# 102709.net
KiCad netlist of a schematic drawn in Altium Designer
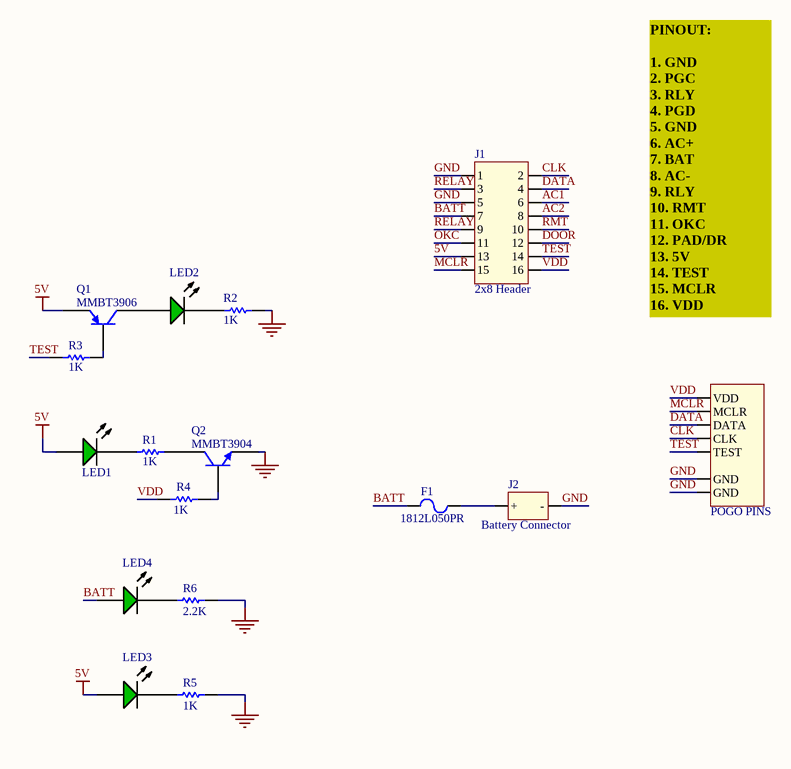
[diagram p0: 102709.SchDoc]

(export (version "E")
  (design (tool "Eeschema 10.0.6"))
  (components
    (comp (ref "F1")
      (value "1812L050PR")
      (footprint "LFUS-1812L050_V")
      (fields (field (name "TOLERANCE") "1%"))
      (libsource (lib "Altium Content Vault") (part "CMP-1700-00002-1"))
    )
    (comp (ref "J1")
      (value "2x8 Header")
      (footprint "2x9_header")
      (libsource (lib "102709") (part "2x9 Header"))
    )
    (comp (ref "J2")
      (value "Battery Connector")
      (footprint "Battery Connector")
      (libsource (lib "102709") (part "Battery Connector"))
    )
    (comp (ref "LED1")
      (value "HSMG-C150")
      (footprint "AVAG-HSMX-C150_V")
      (description "Chip LED, Green, 65 mW, 25 mA, -40 to 85 degC, 2-Pin SMD, RoHS, Tape and Reel")
      (fields (field (name "MANUFACTURER") "Avago"))
      (libsource (lib "altium-import") (part "root_0__Altium Content Vault"))
    )
    (comp (ref "LED2")
      (value "HSMG-C150")
      (footprint "AVAG-HSMX-C150_V")
      (description "Chip LED, Green, 65 mW, 25 mA, -40 to 85 degC, 2-Pin SMD, RoHS, Tape and Reel")
      (fields (field (name "MANUFACTURER") "Avago"))
      (libsource (lib "altium-import") (part "root_0__Altium Content Vault"))
    )
    (comp (ref "LED3")
      (value "HSMG-C150")
      (footprint "AVAG-HSMX-C150_V")
      (description "Chip LED, Green, 65 mW, 25 mA, -40 to 85 degC, 2-Pin SMD, RoHS, Tape and Reel")
      (fields (field (name "MANUFACTURER") "Avago"))
      (libsource (lib "altium-import") (part "root_0__Altium Content Vault"))
    )
    (comp (ref "LED4")
      (value "HSMG-C150")
      (footprint "AVAG-HSMX-C150_V")
      (description "Chip LED, Green, 65 mW, 25 mA, -40 to 85 degC, 2-Pin SMD, RoHS, Tape and Reel")
      (fields (field (name "MANUFACTURER") "Avago"))
      (libsource (lib "altium-import") (part "root_0__Altium Content Vault"))
    )
    (comp (ref "P1")
      (value "POGO PINS")
      (footprint "EAX500 POGOS")
      (libsource (lib "102709") (part "EAX500 POGO"))
    )
    (comp (ref "Q1")
      (value "MMBT3906")
      (footprint "FAIR-SOT23-3_V")
      (description "PNP General-Purpose Amplifier, 40 V, 0.2 A, -55 to 150 degC, 3-Pin SOT23, RoHS, Tape and Reel")
      (fields (field (name "TOLERANCE") "20%"))
      (libsource (lib "Altium Content Vault") (part "CMP-1670-00011-1"))
    )
    (comp (ref "Q2")
      (value "MMBT3904")
      (footprint "FAIR-SOT23-3_V")
      (description "NPN General Purpose Amplifier, 40 V, 0.2 A, -55 to 150 degC, 3-Pin SOT23, RoHS, Tape and Reel")
      (fields (field (name "TOLERANCE") "30ppm"))
      (libsource (lib "Altium Content Vault") (part "CMP-1670-00008-1"))
    )
    (comp (ref "R1")
      (value "1K")
      (footprint "RESC0805(2012)_M")
      (description "Resistor")
      (fields (field (name "Comment") "Res1") (field (name "PUBLISHER") "Altium Limited"))
      (libsource (lib "Miscellaneous Devices") (part "Res1"))
    )
    (comp (ref "R2")
      (value "1K")
      (footprint "RESC0805(2012)_M")
      (description "Resistor")
      (fields (field (name "Comment") "Res1") (field (name "PUBLISHER") "Altium Limited"))
      (libsource (lib "Miscellaneous Devices") (part "Res1"))
    )
    (comp (ref "R3")
      (value "1K")
      (footprint "RESC0805(2012)_M")
      (description "Resistor")
      (fields (field (name "Comment") "Res1") (field (name "PUBLISHER") "Altium Limited"))
      (libsource (lib "Miscellaneous Devices") (part "Res1"))
    )
    (comp (ref "R4")
      (value "1K")
      (footprint "RESC0805(2012)_M")
      (description "Resistor")
      (fields (field (name "Comment") "Res1") (field (name "PUBLISHER") "Altium Limited"))
      (libsource (lib "Miscellaneous Devices") (part "Res1"))
    )
    (comp (ref "R5")
      (value "1K")
      (footprint "RESC0805(2012)_M")
      (description "Resistor")
      (fields (field (name "Comment") "Res1") (field (name "PUBLISHER") "Altium Limited"))
      (libsource (lib "Miscellaneous Devices") (part "Res1"))
    )
    (comp (ref "R6")
      (value "2.2K")
      (footprint "RESC0805(2012)_M")
      (description "Resistor")
      (fields (field (name "Comment") "Res1") (field (name "PUBLISHER") "Altium Limited"))
      (libsource (lib "Miscellaneous Devices") (part "Res1"))
    )
  )
  (nets
    (net (code "1") (name "/AC1") (class "Default")
      (node (ref "J1") (pin "6") (pinfunction "6_6") (pintype "passive"))
    )
    (net (code "2") (name "/AC2") (class "Default")
      (node (ref "J1") (pin "8") (pinfunction "8_8") (pintype "passive"))
    )
    (net (code "3") (name "/BATT") (class "Default")
      (node (ref "F1") (pin "1") (pinfunction "1_1") (pintype "passive"))
      (node (ref "J1") (pin "7") (pinfunction "7_7") (pintype "passive"))
      (node (ref "LED4") (pin "1") (pinfunction "A_1") (pintype "passive"))
    )
    (net (code "4") (name "/CLK") (class "Default")
      (node (ref "J1") (pin "2") (pinfunction "2_2") (pintype "passive"))
      (node (ref "P1") (pin "3") (pinfunction "CLK_3") (pintype "passive"))
    )
    (net (code "5") (name "/DATA") (class "Default")
      (node (ref "J1") (pin "4") (pinfunction "4_4") (pintype "passive"))
      (node (ref "P1") (pin "4") (pinfunction "DATA_4") (pintype "passive"))
    )
    (net (code "6") (name "/DOOR") (class "Default")
      (node (ref "J1") (pin "12") (pinfunction "12_12") (pintype "passive"))
    )
    (net (code "7") (name "/MCLR") (class "Default")
      (node (ref "J1") (pin "15") (pinfunction "15_15") (pintype "passive"))
      (node (ref "P1") (pin "5") (pinfunction "MCLR_5") (pintype "passive"))
    )
    (net (code "8") (name "/OKC") (class "Default")
      (node (ref "J1") (pin "11") (pinfunction "11_11") (pintype "passive"))
    )
    (net (code "9") (name "/RELAY") (class "Default")
      (node (ref "J1") (pin "3") (pinfunction "3_3") (pintype "passive"))
      (node (ref "J1") (pin "9") (pinfunction "9_9") (pintype "passive"))
    )
    (net (code "10") (name "/RMT") (class "Default")
      (node (ref "J1") (pin "10") (pinfunction "10_10") (pintype "passive"))
    )
    (net (code "11") (name "/TEST") (class "Default")
      (node (ref "J1") (pin "14") (pinfunction "14_14") (pintype "passive"))
      (node (ref "P1") (pin "7") (pinfunction "TEST_7") (pintype "passive"))
      (node (ref "R3") (pin "2") (pinfunction "2_2") (pintype "passive"))
    )
    (net (code "12") (name "/VDD") (class "Default")
      (node (ref "J1") (pin "16") (pinfunction "16_16") (pintype "passive"))
      (node (ref "P1") (pin "6") (pinfunction "VDD_6") (pintype "passive"))
      (node (ref "R4") (pin "1") (pinfunction "1_1") (pintype "passive"))
    )
    (net (code "13") (name "5V") (class "Default")
      (node (ref "J1") (pin "13") (pinfunction "13_13") (pintype "passive"))
      (node (ref "LED1") (pin "1") (pinfunction "A_1") (pintype "passive"))
      (node (ref "LED3") (pin "1") (pinfunction "A_1") (pintype "passive"))
      (node (ref "Q1") (pin "2") (pinfunction "E_2") (pintype "passive"))
    )
    (net (code "14") (name "GND") (class "Default")
      (node (ref "J1") (pin "1") (pinfunction "1_1") (pintype "passive"))
      (node (ref "J1") (pin "5") (pinfunction "5_5") (pintype "passive"))
      (node (ref "J2") (pin "2") (pinfunction "-_2") (pintype "passive"))
      (node (ref "P1") (pin "2") (pinfunction "GND_2") (pintype "passive"))
      (node (ref "P1") (pin "8") (pinfunction "GND_8") (pintype "passive"))
      (node (ref "Q2") (pin "2") (pinfunction "E_2") (pintype "passive"))
      (node (ref "R2") (pin "2") (pinfunction "2_2") (pintype "passive"))
      (node (ref "R5") (pin "2") (pinfunction "2_2") (pintype "passive"))
      (node (ref "R6") (pin "2") (pinfunction "2_2") (pintype "passive"))
    )
    (net (code "15") (name "Net-(J2-+)") (class "Default")
      (node (ref "F1") (pin "2") (pinfunction "2_2") (pintype "passive"))
      (node (ref "J2") (pin "1") (pinfunction "+_1") (pintype "passive"))
    )
    (net (code "16") (name "Net-(LED1-K)") (class "Default")
      (node (ref "LED1") (pin "2") (pinfunction "K_2") (pintype "passive"))
      (node (ref "R1") (pin "1") (pinfunction "1_1") (pintype "passive"))
    )
    (net (code "17") (name "Net-(LED2-A)") (class "Default")
      (node (ref "LED2") (pin "1") (pinfunction "A_1") (pintype "passive"))
      (node (ref "Q1") (pin "3") (pinfunction "C_3") (pintype "passive"))
    )
    (net (code "18") (name "Net-(LED2-K)") (class "Default")
      (node (ref "LED2") (pin "2") (pinfunction "K_2") (pintype "passive"))
      (node (ref "R2") (pin "1") (pinfunction "1_1") (pintype "passive"))
    )
    (net (code "19") (name "Net-(LED3-K)") (class "Default")
      (node (ref "LED3") (pin "2") (pinfunction "K_2") (pintype "passive"))
      (node (ref "R5") (pin "1") (pinfunction "1_1") (pintype "passive"))
    )
    (net (code "20") (name "Net-(LED4-K)") (class "Default")
      (node (ref "LED4") (pin "2") (pinfunction "K_2") (pintype "passive"))
      (node (ref "R6") (pin "1") (pinfunction "1_1") (pintype "passive"))
    )
    (net (code "21") (name "Net-(Q1-B)") (class "Default")
      (node (ref "Q1") (pin "1") (pinfunction "B_1") (pintype "passive"))
      (node (ref "R3") (pin "1") (pinfunction "1_1") (pintype "passive"))
    )
    (net (code "22") (name "Net-(Q2-B)") (class "Default")
      (node (ref "Q2") (pin "1") (pinfunction "B_1") (pintype "passive"))
      (node (ref "R4") (pin "2") (pinfunction "2_2") (pintype "passive"))
    )
    (net (code "23") (name "Net-(Q2-C)") (class "Default")
      (node (ref "Q2") (pin "3") (pinfunction "C_3") (pintype "passive"))
      (node (ref "R1") (pin "2") (pinfunction "2_2") (pintype "passive"))
    )
  )
)
